# Sheet1.net
KiCad netlist of a schematic drawn in Altium Designer
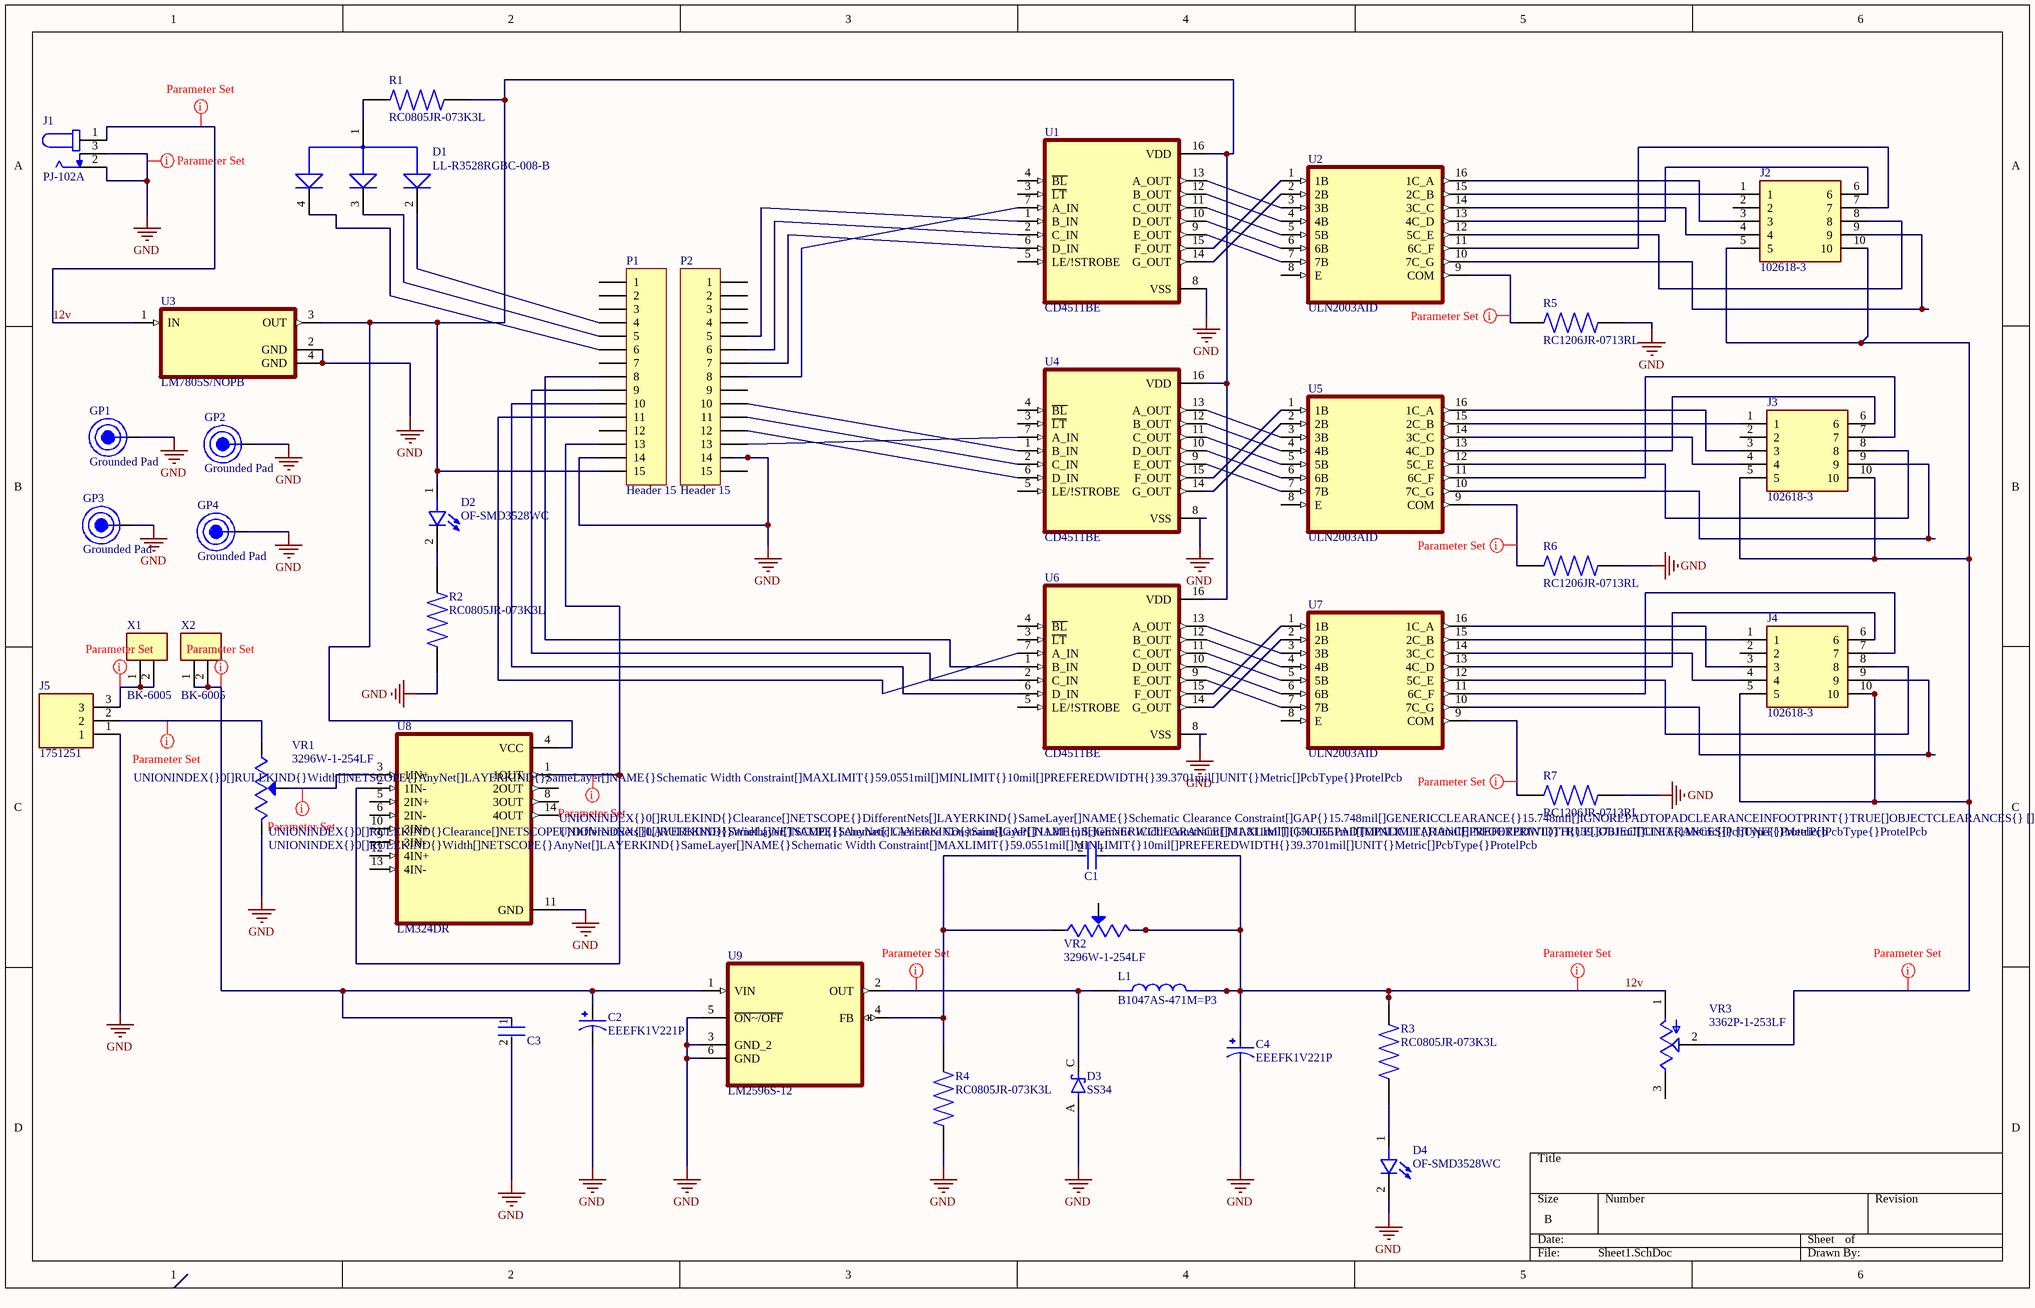
[diagram p0: Sheet1.SchDoc]

(export (version "E")
  (design (tool "Eeschema 10.0.6"))
  (components
    (comp (ref "C1")
      (value "C0805C104K5RAC")
      (footprint "KEMET_C0805C-DN_IPC_C")
      (libsource (lib "Cap_KEMET_C0805C104K5RAC_eec") (part "C0805C104K5RAC"))
    )
    (comp (ref "C2")
      (value "EEEFK1V221P")
      (footprint "CAP_EEEFK1V221P")
      (description "220ÂµF 35V Aluminum Electrolytic Capacitors Radial, Can - SMD 2000 Hrs @ 105Â°C")
      (fields (field (name "MF") "Panasonic"))
      (libsource (lib "EEEFK1V221P") (part "EEEFK1V221P"))
    )
    (comp (ref "C3")
      (value "C0805C104K5RAC")
      (footprint "KEMET_C0805C-DN_IPC_C")
      (libsource (lib "Cap_KEMET_C0805C104K5RAC_eec") (part "C0805C104K5RAC"))
    )
    (comp (ref "C4")
      (value "EEEFK1V221P")
      (footprint "CAP_EEEFK1V221P")
      (description "220ÂµF 35V Aluminum Electrolytic Capacitors Radial, Can - SMD 2000 Hrs @ 105Â°C")
      (fields (field (name "MF") "Panasonic"))
      (libsource (lib "EEEFK1V221P") (part "EEEFK1V221P"))
    )
    (comp (ref "D1")
      (value "LL-R3528RGBC-008-B")
      (footprint "LED_LL-R3528RGBC-008-B")
      (description "LED; SMD; 3528, PLCC2; RGB; 3.5x2.8mm; 120Â°; Red lumin: 1")
      (fields (field (name "MF") "Lucky Light"))
      (libsource (lib "LL-R3528RGBC-008-B") (part "LL-R3528RGBC-008-B"))
    )
    (comp (ref "D2")
      (value "OF-SMD3528WC")
      (footprint "LED_OF-SMD3528WC")
      (description "LED; SMD; 3528, PLCC2; white cold; 1700-2500mcd; 120Â°; 2")
      (fields (field (name "MF") "Optoflash"))
      (libsource (lib "OF-SMD3528WC") (part "OF-SMD3528WC"))
    )
    (comp (ref "D3")
      (value "SS34")
      (footprint "DIOM7959X265N")
      (description "Diode Schottky 40V 3A Surface Mount SMC _DO-214AB_")
      (fields (field (name "MF") "ON Semiconductor"))
      (libsource (lib "SS34") (part "SS34"))
    )
    (comp (ref "D4")
      (value "OF-SMD3528WC")
      (footprint "LED_OF-SMD3528WC")
      (description "LED; SMD; 3528, PLCC2; white cold; 1700-2500mcd; 120Â°; 2")
      (fields (field (name "MF") "Optoflash"))
      (libsource (lib "OF-SMD3528WC") (part "OF-SMD3528WC"))
    )
    (comp (ref "GP1")
      (value "Grounded Pad")
      (footprint "2.75mm Grounded Pad")
      (description "2.75mm Diameter Grounded Pad")
      (libsource (lib "Misc_Tools") (part "2.75mm Grounded Pad"))
    )
    (comp (ref "GP2")
      (value "Grounded Pad")
      (footprint "2.75mm Grounded Pad")
      (description "2.75mm Diameter Grounded Pad")
      (libsource (lib "Misc_Tools") (part "2.75mm Grounded Pad"))
    )
    (comp (ref "GP3")
      (value "Grounded Pad")
      (footprint "2.75mm Grounded Pad")
      (description "2.75mm Diameter Grounded Pad")
      (libsource (lib "Misc_Tools") (part "2.75mm Grounded Pad"))
    )
    (comp (ref "GP4")
      (value "Grounded Pad")
      (footprint "2.75mm Grounded Pad")
      (description "2.75mm Diameter Grounded Pad")
      (libsource (lib "Misc_Tools") (part "2.75mm Grounded Pad"))
    )
    (comp (ref "J1")
      (value "PJ-102A")
      (footprint "CUI_PJ-102A")
      (description "2.0 x 6.5 mm, 2.5 A, Horizontal, Through Hole, Tapered Pins, Dc Power Jack Connector")
      (fields (field (name "MF") "CUI Devices"))
      (libsource (lib "PJ-102A") (part "PJ-102A"))
    )
    (comp (ref "J2")
      (value "102618-3")
      (footprint "TE_102618-3")
      (description "10 MODII HDR DRST SHRD .100CL")
      (libsource (lib "102618-3") (part "102618-3"))
    )
    (comp (ref "J3")
      (value "102618-3")
      (footprint "TE_102618-3")
      (description "10 MODII HDR DRST SHRD .100CL")
      (libsource (lib "102618-3") (part "102618-3"))
    )
    (comp (ref "J4")
      (value "102618-3")
      (footprint "TE_102618-3")
      (description "10 MODII HDR DRST SHRD .100CL")
      (libsource (lib "102618-3") (part "102618-3"))
    )
    (comp (ref "J5")
      (value "1751251")
      (footprint "PHOENIX_1751251")
      (description "3 Position Wire to Board Terminal Block Horizontal with Board 0.138 _3.50mm_ Through Hole")
      (fields (field (name "MF") "Phoenix Contact"))
      (libsource (lib "1751251") (part "1751251"))
    )
    (comp (ref "L1")
      (value "B1047AS-471M=P3")
      (footprint "IND_B1047AS-471M=P3")
      (description "Inductor Power Shielded Wirewound 220uH 20% 100KHz Ferrite 470mA 1.1Ohm DCR 2929 T/R")
      (libsource (lib "B1047AS-471M_P3") (part "B1047AS-471M=P3"))
    )
    (comp (ref "P1")
      (value "Header 15")
      (footprint "HDR1X15")
      (description "Header, 15-Pin")
      (fields (field (name "PUBLISHER") "Altium Limited"))
      (libsource (lib "Miscellaneous Connectors") (part "Header 15"))
    )
    (comp (ref "P2")
      (value "Header 15")
      (footprint "HDR1X15")
      (description "Header, 15-Pin")
      (fields (field (name "PUBLISHER") "Altium Limited"))
      (libsource (lib "") (part "Header 15_1"))
    )
    (comp (ref "R1")
      (value "RC0805JR-073K3L")
      (footprint "RESC2012X60N")
      (description "RC Series 0805 0.125 W 3.3 kOhms 5% Â±100 ppm/Â°C SMT Thick Film Chip Resistor")
      (libsource (lib "RC0805JR-073K3L") (part "RC0805JR-073K3L"))
    )
    (comp (ref "R2")
      (value "RC0805JR-073K3L")
      (footprint "RESC2012X60N")
      (description "RC Series 0805 0.125 W 3.3 kOhms 5% Â±100 ppm/Â°C SMT Thick Film Chip Resistor")
      (libsource (lib "RC0805JR-073K3L") (part "RC0805JR-073K3L"))
    )
    (comp (ref "R3")
      (value "RC0805JR-073K3L")
      (footprint "RESC2012X60N")
      (description "RC Series 0805 0.125 W 3.3 kOhms 5% Â±100 ppm/Â°C SMT Thick Film Chip Resistor")
      (libsource (lib "RC0805JR-073K3L") (part "RC0805JR-073K3L"))
    )
    (comp (ref "R4")
      (value "RC0805JR-073K3L")
      (footprint "RESC2012X60N")
      (description "RC Series 0805 0.125 W 3.3 kOhms 5% Â±100 ppm/Â°C SMT Thick Film Chip Resistor")
      (libsource (lib "RC0805JR-073K3L") (part "RC0805JR-073K3L"))
    )
    (comp (ref "R5")
      (value "RC1206JR-0713RL")
      (footprint "RESC3116X65N")
      (description "13 Ohms Â±5% 0.25W, 1/4W Chip Resistor 1206 _3216 Metric_ Moisture Resistant Thick Film")
      (fields (field (name "MF") "Yageo"))
      (libsource (lib "RC1206JR-0713RL") (part "RC1206JR-0713RL"))
    )
    (comp (ref "R6")
      (value "RC1206JR-0713RL")
      (footprint "RESC3116X65N")
      (description "13 Ohms Â±5% 0.25W, 1/4W Chip Resistor 1206 _3216 Metric_ Moisture Resistant Thick Film")
      (fields (field (name "MF") "Yageo"))
      (libsource (lib "RC1206JR-0713RL") (part "RC1206JR-0713RL"))
    )
    (comp (ref "R7")
      (value "RC1206JR-0713RL")
      (footprint "RESC3116X65N")
      (description "13 Ohms Â±5% 0.25W, 1/4W Chip Resistor 1206 _3216 Metric_ Moisture Resistant Thick Film")
      (fields (field (name "MF") "Yageo"))
      (libsource (lib "RC1206JR-0713RL") (part "RC1206JR-0713RL"))
    )
    (comp (ref "U1")
      (value "CD4511BE")
      (footprint "DIP794W45P254L1969H508Q16")
      (description "CMOS BCD-to-7-Segment LED Latch Decoder Drivers 16-PDIP -55 to 125")
      (fields (field (name "MF") "Texas Instruments"))
      (libsource (lib "CD4511BE") (part "CD4511BE"))
    )
    (comp (ref "U2")
      (value "ULN2003AID")
      (footprint "SOIC127P600X175-16N")
      (description "50-V, 7-ch darlington transistor array, -40 to 105C 16-SOIC -40 to 105")
      (fields (field (name "DIGI-KEY_PART_NUMBER") "296-15407-2-ND") (field (name "MF") "Texas Instruments"))
      (libsource (lib "ULN2003AID") (part "ULN2003AID"))
    )
    (comp (ref "U3")
      (value "LM7805S/NOPB")
      (footprint "TO254P1524X483-4N")
      (description "1.5-A, 30-V, linear voltage regulator 3-DDPAK/TO-263 0 to 125")
      (fields (field (name "MF") "Texas Instruments"))
      (libsource (lib "LM7805S_NOPB") (part "LM7805S/NOPB"))
    )
    (comp (ref "U4")
      (value "CD4511BE")
      (footprint "DIP794W45P254L1969H508Q16")
      (description "CMOS BCD-to-7-Segment LED Latch Decoder Drivers 16-PDIP -55 to 125")
      (fields (field (name "MF") "Texas Instruments"))
      (libsource (lib "CD4511BE") (part "CD4511BE"))
    )
    (comp (ref "U5")
      (value "ULN2003AID")
      (footprint "SOIC127P600X175-16N")
      (description "50-V, 7-ch darlington transistor array, -40 to 105C 16-SOIC -40 to 105")
      (fields (field (name "DIGI-KEY_PART_NUMBER") "296-15407-2-ND") (field (name "MF") "Texas Instruments"))
      (libsource (lib "ULN2003AID") (part "ULN2003AID"))
    )
    (comp (ref "U6")
      (value "CD4511BE")
      (footprint "DIP794W45P254L1969H508Q16")
      (description "CMOS BCD-to-7-Segment LED Latch Decoder Drivers 16-PDIP -55 to 125")
      (fields (field (name "MF") "Texas Instruments"))
      (libsource (lib "CD4511BE") (part "CD4511BE"))
    )
    (comp (ref "U7")
      (value "ULN2003AID")
      (footprint "SOIC127P600X175-16N")
      (description "50-V, 7-ch darlington transistor array, -40 to 105C 16-SOIC -40 to 105")
      (fields (field (name "DIGI-KEY_PART_NUMBER") "296-15407-2-ND") (field (name "MF") "Texas Instruments"))
      (libsource (lib "ULN2003AID") (part "ULN2003AID"))
    )
    (comp (ref "U8")
      (value "LM324DR")
      (footprint "SOIC127P600X175-14N")
      (description "4-Channel industry standard operational amplifier 14-SOIC 0 to 70")
      (fields (field (name "MF") "Texas Instruments"))
      (libsource (lib "LM324DR") (part "LM324DR"))
    )
    (comp (ref "U9")
      (value "LM2596S-12")
      (footprint "TO170P1435X465-6N")
      (fields (field (name "MF") "Texas Instruments"))
      (libsource (lib "LM2596S-12") (part "LM2596S-12"))
    )
    (comp (ref "VR1")
      (value "3296W-1-254LF")
      (footprint "TRIM_3296W-1-254LF")
      (description "250 kOhms 0.5W, 1/2W PC Pins Through Hole Trimmer Potentiometer Cermet 25 Turn Top Adjustment")
      (fields (field (name "MF") "Bourns"))
      (libsource (lib "3296W-1-254LF") (part "3296W-1-254LF"))
    )
    (comp (ref "VR2")
      (value "3296W-1-254LF")
      (footprint "TRIM_3296W-1-254LF")
      (description "250 kOhms 0.5W, 1/2W PC Pins Through Hole Trimmer Potentiometer Cermet 25 Turn Top Adjustment")
      (fields (field (name "MF") "Bourns"))
      (libsource (lib "3296W-1-254LF") (part "3296W-1-254LF"))
    )
    (comp (ref "VR3")
      (value "3362P-1-253LF")
      (footprint "TRIM_3362P-1-253LF")
      (description "25 kOhms 0.5W, 1/2W PC Pins Through Hole Trimmer Potentiometer Cermet 1 Turn Top Adjustment")
      (fields (field (name "MF") "Bourns"))
      (libsource (lib "3362P-1-253LF") (part "3362P-1-253LF"))
    )
    (comp (ref "X1")
      (value "BK-6005")
      (footprint "FUSE_BK-6005")
      (description "Fuse Clip 1 Circuit Cartridge Through Hole")
      (fields (field (name "MF") "MPD"))
      (libsource (lib "BK-6005") (part "BK-6005"))
    )
    (comp (ref "X2")
      (value "BK-6005")
      (footprint "FUSE_BK-6005")
      (description "Fuse Clip 1 Circuit Cartridge Through Hole")
      (fields (field (name "MF") "MPD"))
      (libsource (lib "BK-6005") (part "BK-6005"))
    )
  )
  (nets
    (net (code "1") (name "/12v") (class "Default")
      (node (ref "C1") (pin "1") (pinfunction "1_1") (pintype "passive"))
      (node (ref "C4") (pin "1") (pinfunction "1_1") (pintype "passive"))
      (node (ref "J1") (pin "1") (pinfunction "1_1") (pintype "passive"))
      (node (ref "L1") (pin "2") (pinfunction "2_2") (pintype "passive"))
      (node (ref "R3") (pin "2") (pinfunction "2_2") (pintype "passive"))
      (node (ref "U3") (pin "1") (pinfunction "IN_1") (pintype "input"))
      (node (ref "VR2") (pin "3") (pinfunction "CW_3") (pintype "passive"))
      (node (ref "VR3") (pin "1") (pinfunction "CCW_1") (pintype "passive"))
    )
    (net (code "2") (name "GND") (class "Default")
      (node (ref "C2") (pin "2") (pinfunction "2_2") (pintype "passive"))
      (node (ref "C3") (pin "2") (pinfunction "2_2") (pintype "passive"))
      (node (ref "C4") (pin "2") (pinfunction "2_2") (pintype "passive"))
      (node (ref "D3") (pin "A") (pinfunction "A_A") (pintype "passive"))
      (node (ref "D4") (pin "2") (pinfunction "C_2") (pintype "passive"))
      (node (ref "GP1") (pin "1") (pinfunction "1_1") (pintype "passive"))
      (node (ref "GP2") (pin "1") (pinfunction "1_1") (pintype "passive"))
      (node (ref "GP3") (pin "1") (pinfunction "1_1") (pintype "passive"))
      (node (ref "GP4") (pin "1") (pinfunction "1_1") (pintype "passive"))
      (node (ref "J1") (pin "2") (pinfunction "2_2") (pintype "passive"))
      (node (ref "J1") (pin "3") (pinfunction "3_3") (pintype "passive"))
      (node (ref "J5") (pin "1") (pinfunction "1_1") (pintype "passive"))
      (node (ref "P1") (pin "14") (pinfunction "14_14") (pintype "passive"))
      (node (ref "P2") (pin "14") (pinfunction "14_14") (pintype "passive"))
      (node (ref "R2") (pin "1") (pinfunction "1_1") (pintype "passive"))
      (node (ref "R4") (pin "1") (pinfunction "1_1") (pintype "passive"))
      (node (ref "R5") (pin "2") (pinfunction "2_2") (pintype "passive"))
      (node (ref "R6") (pin "2") (pinfunction "2_2") (pintype "passive"))
      (node (ref "R7") (pin "2") (pinfunction "2_2") (pintype "passive"))
      (node (ref "U1") (pin "8") (pinfunction "VSS_8") (pintype "power_in"))
      (node (ref "U3") (pin "2") (pinfunction "GND_2") (pintype "power_in"))
      (node (ref "U3") (pin "4") (pinfunction "GND_4") (pintype "power_in"))
      (node (ref "U4") (pin "8") (pinfunction "VSS_8") (pintype "power_in"))
      (node (ref "U6") (pin "8") (pinfunction "VSS_8") (pintype "power_in"))
      (node (ref "U8") (pin "11") (pinfunction "GND_11") (pintype "power_in"))
      (node (ref "U9") (pin "3") (pinfunction "GND_2_3") (pintype "passive"))
      (node (ref "U9") (pin "5") (pinfunction "~{ON~/OFF}_5") (pintype "passive"))
      (node (ref "U9") (pin "6") (pinfunction "GND_6") (pintype "passive"))
      (node (ref "VR1") (pin "3") (pinfunction "CW_3") (pintype "passive"))
    )
    (net (code "3") (name "Net-(D1-CATHODE_BLUE)") (class "Default")
      (node (ref "D1") (pin "4") (pinfunction "CATHODE_BLUE_4") (pintype "passive"))
      (node (ref "P1") (pin "6") (pinfunction "6_6") (pintype "passive"))
    )
    (net (code "4") (name "Net-(D1-CATHODE_GREEN)") (class "Default")
      (node (ref "D1") (pin "3") (pinfunction "CATHODE_GREEN_3") (pintype "passive"))
      (node (ref "P1") (pin "5") (pinfunction "5_5") (pintype "passive"))
    )
    (net (code "5") (name "Net-(D1-CATHODE_RED)") (class "Default")
      (node (ref "D1") (pin "2") (pinfunction "CATHODE_RED_2") (pintype "passive"))
      (node (ref "P1") (pin "4") (pinfunction "4_4") (pintype "passive"))
    )
    (net (code "6") (name "Net-(D1-COMM_ANODE)") (class "Default")
      (node (ref "D1") (pin "1") (pinfunction "COMM_ANODE_1") (pintype "passive"))
      (node (ref "R1") (pin "2") (pinfunction "2_2") (pintype "passive"))
    )
    (net (code "7") (name "Net-(D2-A)") (class "Default")
      (node (ref "D2") (pin "1") (pinfunction "A_1") (pintype "passive"))
      (node (ref "P1") (pin "15") (pinfunction "15_15") (pintype "passive"))
      (node (ref "R1") (pin "1") (pinfunction "1_1") (pintype "passive"))
      (node (ref "U1") (pin "16") (pinfunction "VDD_16") (pintype "power_in"))
      (node (ref "U3") (pin "3") (pinfunction "OUT_3") (pintype "output"))
      (node (ref "U4") (pin "16") (pinfunction "VDD_16") (pintype "power_in"))
      (node (ref "U6") (pin "16") (pinfunction "VDD_16") (pintype "power_in"))
      (node (ref "U8") (pin "4") (pinfunction "VCC_4") (pintype "power_in"))
    )
    (net (code "8") (name "Net-(D2-C)") (class "Default")
      (node (ref "D2") (pin "2") (pinfunction "C_2") (pintype "passive"))
      (node (ref "R2") (pin "2") (pinfunction "2_2") (pintype "passive"))
    )
    (net (code "9") (name "Net-(D3-K)") (class "Default")
      (node (ref "D3") (pin "C") (pinfunction "K_C") (pintype "passive"))
      (node (ref "L1") (pin "1") (pinfunction "1_1") (pintype "passive"))
      (node (ref "U9") (pin "2") (pinfunction "OUT_2") (pintype "output"))
    )
    (net (code "10") (name "Net-(D4-A)") (class "Default")
      (node (ref "D4") (pin "1") (pinfunction "A_1") (pintype "passive"))
      (node (ref "R3") (pin "1") (pinfunction "1_1") (pintype "passive"))
    )
    (net (code "11") (name "Net-(J5-Pad3)") (class "Default")
      (node (ref "J5") (pin "3") (pinfunction "3_3") (pintype "passive"))
      (node (ref "X1") (pin "1") (pinfunction "1_1") (pintype "passive"))
      (node (ref "X1") (pin "2") (pinfunction "1_2") (pintype "passive"))
    )
    (net (code "12") (name "Net-(U1-A_IN)") (class "Default")
      (node (ref "P2") (pin "8") (pinfunction "8_8") (pintype "passive"))
      (node (ref "U1") (pin "7") (pinfunction "A_IN_7") (pintype "input"))
    )
    (net (code "13") (name "Net-(U1-A_OUT)") (class "Default")
      (node (ref "U1") (pin "13") (pinfunction "A_OUT_13") (pintype "output"))
      (node (ref "U2") (pin "3") (pinfunction "3B_3") (pintype "input"))
    )
    (net (code "14") (name "Net-(U1-B_IN)") (class "Default")
      (node (ref "P2") (pin "5") (pinfunction "5_5") (pintype "passive"))
      (node (ref "U1") (pin "1") (pinfunction "B_IN_1") (pintype "input"))
    )
    (net (code "15") (name "Net-(U1-B_OUT)") (class "Default")
      (node (ref "U1") (pin "12") (pinfunction "B_OUT_12") (pintype "output"))
      (node (ref "U2") (pin "4") (pinfunction "4B_4") (pintype "input"))
    )
    (net (code "16") (name "Net-(U1-C_IN)") (class "Default")
      (node (ref "P2") (pin "6") (pinfunction "6_6") (pintype "passive"))
      (node (ref "U1") (pin "2") (pinfunction "C_IN_2") (pintype "input"))
    )
    (net (code "17") (name "Net-(U1-C_OUT)") (class "Default")
      (node (ref "U1") (pin "11") (pinfunction "C_OUT_11") (pintype "output"))
      (node (ref "U2") (pin "5") (pinfunction "5B_5") (pintype "input"))
    )
    (net (code "18") (name "Net-(U1-D_IN)") (class "Default")
      (node (ref "P2") (pin "7") (pinfunction "7_7") (pintype "passive"))
      (node (ref "U1") (pin "6") (pinfunction "D_IN_6") (pintype "input"))
    )
    (net (code "19") (name "Net-(U1-D_OUT)") (class "Default")
      (node (ref "U1") (pin "10") (pinfunction "D_OUT_10") (pintype "output"))
      (node (ref "U2") (pin "6") (pinfunction "6B_6") (pintype "input"))
    )
    (net (code "20") (name "Net-(U1-E_OUT)") (class "Default")
      (node (ref "U1") (pin "9") (pinfunction "E_OUT_9") (pintype "output"))
      (node (ref "U2") (pin "7") (pinfunction "7B_7") (pintype "input"))
    )
    (net (code "21") (name "Net-(U1-F_OUT)") (class "Default")
      (node (ref "U1") (pin "15") (pinfunction "F_OUT_15") (pintype "output"))
      (node (ref "U2") (pin "1") (pinfunction "1B_1") (pintype "input"))
    )
    (net (code "22") (name "Net-(U1-G_OUT)") (class "Default")
      (node (ref "U1") (pin "14") (pinfunction "G_OUT_14") (pintype "output"))
      (node (ref "U2") (pin "2") (pinfunction "2B_2") (pintype "input"))
    )
    (net (code "23") (name "Net-(U2-1C_A)") (class "Default")
      (node (ref "J2") (pin "3") (pinfunction "3_3") (pintype "passive"))
      (node (ref "U2") (pin "16") (pinfunction "1C_A_16") (pintype "output"))
    )
    (net (code "24") (name "Net-(U2-2C_B)") (class "Default")
      (node (ref "J2") (pin "1") (pinfunction "1_1") (pintype "passive"))
      (node (ref "U2") (pin "15") (pinfunction "2C_B_15") (pintype "output"))
    )
    (net (code "25") (name "Net-(U2-3C_C)") (class "Default")
      (node (ref "J2") (pin "4") (pinfunction "4_4") (pintype "passive"))
      (node (ref "U2") (pin "14") (pinfunction "3C_C_14") (pintype "output"))
    )
    (net (code "26") (name "Net-(U2-4C_D)") (class "Default")
      (node (ref "J2") (pin "6") (pinfunction "6_6") (pintype "passive"))
      (node (ref "U2") (pin "13") (pinfunction "4C_D_13") (pintype "output"))
    )
    (net (code "27") (name "Net-(U2-5C_E)") (class "Default")
      (node (ref "J2") (pin "8") (pinfunction "8_8") (pintype "passive"))
      (node (ref "U2") (pin "12") (pinfunction "5C_E_12") (pintype "output"))
    )
    (net (code "28") (name "Net-(U2-6C_F)") (class "Default")
      (node (ref "J2") (pin "7") (pinfunction "7_7") (pintype "passive"))
      (node (ref "U2") (pin "11") (pinfunction "6C_F_11") (pintype "output"))
    )
    (net (code "29") (name "Net-(U2-7C_G)") (class "Default")
      (node (ref "J2") (pin "9") (pinfunction "9_9") (pintype "passive"))
      (node (ref "U2") (pin "10") (pinfunction "7C_G_10") (pintype "output"))
    )
    (net (code "30") (name "Net-(U2-COM)") (class "Default")
      (node (ref "R5") (pin "1") (pinfunction "1_1") (pintype "passive"))
      (node (ref "U2") (pin "9") (pinfunction "COM_9") (pintype "output"))
    )
    (net (code "31") (name "Net-(U4-A_IN)") (class "Default")
      (node (ref "P2") (pin "13") (pinfunction "13_13") (pintype "passive"))
      (node (ref "U4") (pin "7") (pinfunction "A_IN_7") (pintype "input"))
    )
    (net (code "32") (name "Net-(U4-A_OUT)") (class "Default")
      (node (ref "U4") (pin "13") (pinfunction "A_OUT_13") (pintype "output"))
      (node (ref "U5") (pin "3") (pinfunction "3B_3") (pintype "input"))
    )
    (net (code "33") (name "Net-(U4-B_IN)") (class "Default")
      (node (ref "P2") (pin "10") (pinfunction "10_10") (pintype "passive"))
      (node (ref "U4") (pin "1") (pinfunction "B_IN_1") (pintype "input"))
    )
    (net (code "34") (name "Net-(U4-B_OUT)") (class "Default")
      (node (ref "U4") (pin "12") (pinfunction "B_OUT_12") (pintype "output"))
      (node (ref "U5") (pin "4") (pinfunction "4B_4") (pintype "input"))
    )
    (net (code "35") (name "Net-(U4-C_IN)") (class "Default")
      (node (ref "P2") (pin "11") (pinfunction "11_11") (pintype "passive"))
      (node (ref "U4") (pin "2") (pinfunction "C_IN_2") (pintype "input"))
    )
    (net (code "36") (name "Net-(U4-C_OUT)") (class "Default")
      (node (ref "U4") (pin "11") (pinfunction "C_OUT_11") (pintype "output"))
      (node (ref "U5") (pin "5") (pinfunction "5B_5") (pintype "input"))
    )
    (net (code "37") (name "Net-(U4-D_IN)") (class "Default")
      (node (ref "P2") (pin "12") (pinfunction "12_12") (pintype "passive"))
      (node (ref "U4") (pin "6") (pinfunction "D_IN_6") (pintype "input"))
    )
    (net (code "38") (name "Net-(U4-D_OUT)") (class "Default")
      (node (ref "U4") (pin "10") (pinfunction "D_OUT_10") (pintype "output"))
      (node (ref "U5") (pin "6") (pinfunction "6B_6") (pintype "input"))
    )
    (net (code "39") (name "Net-(U4-E_OUT)") (class "Default")
      (node (ref "U4") (pin "9") (pinfunction "E_OUT_9") (pintype "output"))
      (node (ref "U5") (pin "7") (pinfunction "7B_7") (pintype "input"))
    )
    (net (code "40") (name "Net-(U4-F_OUT)") (class "Default")
      (node (ref "U4") (pin "15") (pinfunction "F_OUT_15") (pintype "output"))
      (node (ref "U5") (pin "1") (pinfunction "1B_1") (pintype "input"))
    )
    (net (code "41") (name "Net-(U4-G_OUT)") (class "Default")
      (node (ref "U4") (pin "14") (pinfunction "G_OUT_14") (pintype "output"))
      (node (ref "U5") (pin "2") (pinfunction "2B_2") (pintype "input"))
    )
    (net (code "42") (name "Net-(U5-1C_A)") (class "Default")
      (node (ref "J3") (pin "3") (pinfunction "3_3") (pintype "passive"))
      (node (ref "U5") (pin "16") (pinfunction "1C_A_16") (pintype "output"))
    )
    (net (code "43") (name "Net-(U5-2C_B)") (class "Default")
      (node (ref "J3") (pin "1") (pinfunction "1_1") (pintype "passive"))
      (node (ref "U5") (pin "15") (pinfunction "2C_B_15") (pintype "output"))
    )
    (net (code "44") (name "Net-(U5-3C_C)") (class "Default")
      (node (ref "J3") (pin "4") (pinfunction "4_4") (pintype "passive"))
      (node (ref "U5") (pin "14") (pinfunction "3C_C_14") (pintype "output"))
    )
    (net (code "45") (name "Net-(U5-4C_D)") (class "Default")
      (node (ref "J3") (pin "6") (pinfunction "6_6") (pintype "passive"))
      (node (ref "U5") (pin "13") (pinfunction "4C_D_13") (pintype "output"))
    )
    (net (code "46") (name "Net-(U5-5C_E)") (class "Default")
      (node (ref "J3") (pin "8") (pinfunction "8_8") (pintype "passive"))
      (node (ref "U5") (pin "12") (pinfunction "5C_E_12") (pintype "output"))
    )
    (net (code "47") (name "Net-(U5-6C_F)") (class "Default")
      (node (ref "J3") (pin "7") (pinfunction "7_7") (pintype "passive"))
      (node (ref "U5") (pin "11") (pinfunction "6C_F_11") (pintype "output"))
    )
    (net (code "48") (name "Net-(U5-7C_G)") (class "Default")
      (node (ref "J3") (pin "9") (pinfunction "9_9") (pintype "passive"))
      (node (ref "U5") (pin "10") (pinfunction "7C_G_10") (pintype "output"))
    )
    (net (code "49") (name "Net-(U5-COM)") (class "Default")
      (node (ref "R6") (pin "1") (pinfunction "1_1") (pintype "passive"))
      (node (ref "U5") (pin "9") (pinfunction "COM_9") (pintype "output"))
    )
    (net (code "50") (name "Net-(U6-A_IN)") (class "Default")
      (node (ref "P1") (pin "11") (pinfunction "11_11") (pintype "passive"))
      (node (ref "U6") (pin "7") (pinfunction "A_IN_7") (pintype "input"))
    )
    (net (code "51") (name "Net-(U6-A_OUT)") (class "Default")
      (node (ref "U6") (pin "13") (pinfunction "A_OUT_13") (pintype "output"))
      (node (ref "U7") (pin "3") (pinfunction "3B_3") (pintype "input"))
    )
    (net (code "52") (name "Net-(U6-B_IN)") (class "Default")
      (node (ref "P1") (pin "8") (pinfunction "8_8") (pintype "passive"))
      (node (ref "U6") (pin "1") (pinfunction "B_IN_1") (pintype "input"))
    )
    (net (code "53") (name "Net-(U6-B_OUT)") (class "Default")
      (node (ref "U6") (pin "12") (pinfunction "B_OUT_12") (pintype "output"))
      (node (ref "U7") (pin "4") (pinfunction "4B_4") (pintype "input"))
    )
    (net (code "54") (name "Net-(U6-C_IN)") (class "Default")
      (node (ref "P1") (pin "9") (pinfunction "9_9") (pintype "passive"))
      (node (ref "U6") (pin "2") (pinfunction "C_IN_2") (pintype "input"))
    )
    (net (code "55") (name "Net-(U6-C_OUT)") (class "Default")
      (node (ref "U6") (pin "11") (pinfunction "C_OUT_11") (pintype "output"))
      (node (ref "U7") (pin "5") (pinfunction "5B_5") (pintype "input"))
    )
    (net (code "56") (name "Net-(U6-D_IN)") (class "Default")
      (node (ref "P1") (pin "10") (pinfunction "10_10") (pintype "passive"))
      (node (ref "U6") (pin "6") (pinfunction "D_IN_6") (pintype "input"))
    )
    (net (code "57") (name "Net-(U6-D_OUT)") (class "Default")
      (node (ref "U6") (pin "10") (pinfunction "D_OUT_10") (pintype "output"))
      (node (ref "U7") (pin "6") (pinfunction "6B_6") (pintype "input"))
    )
    (net (code "58") (name "Net-(U6-E_OUT)") (class "Default")
      (node (ref "U6") (pin "9") (pinfunction "E_OUT_9") (pintype "output"))
      (node (ref "U7") (pin "7") (pinfunction "7B_7") (pintype "input"))
    )
    (net (code "59") (name "Net-(U6-F_OUT)") (class "Default")
      (node (ref "U6") (pin "15") (pinfunction "F_OUT_15") (pintype "output"))
      (node (ref "U7") (pin "1") (pinfunction "1B_1") (pintype "input"))
    )
    (net (code "60") (name "Net-(U6-G_OUT)") (class "Default")
      (node (ref "U6") (pin "14") (pinfunction "G_OUT_14") (pintype "output"))
      (node (ref "U7") (pin "2") (pinfunction "2B_2") (pintype "input"))
    )
    (net (code "61") (name "Net-(U7-1C_A)") (class "Default")
      (node (ref "J4") (pin "3") (pinfunction "3_3") (pintype "passive"))
      (node (ref "U7") (pin "16") (pinfunction "1C_A_16") (pintype "output"))
    )
    (net (code "62") (name "Net-(U7-2C_B)") (class "Default")
      (node (ref "J4") (pin "1") (pinfunction "1_1") (pintype "passive"))
      (node (ref "U7") (pin "15") (pinfunction "2C_B_15") (pintype "output"))
    )
    (net (code "63") (name "Net-(U7-3C_C)") (class "Default")
      (node (ref "J4") (pin "4") (pinfunction "4_4") (pintype "passive"))
      (node (ref "U7") (pin "14") (pinfunction "3C_C_14") (pintype "output"))
    )
    (net (code "64") (name "Net-(U7-4C_D)") (class "Default")
      (node (ref "J4") (pin "6") (pinfunction "6_6") (pintype "passive"))
      (node (ref "U7") (pin "13") (pinfunction "4C_D_13") (pintype "output"))
    )
    (net (code "65") (name "Net-(U7-5C_E)") (class "Default")
      (node (ref "J4") (pin "8") (pinfunction "8_8") (pintype "passive"))
      (node (ref "U7") (pin "12") (pinfunction "5C_E_12") (pintype "output"))
    )
    (net (code "66") (name "Net-(U7-6C_F)") (class "Default")
      (node (ref "J4") (pin "7") (pinfunction "7_7") (pintype "passive"))
      (node (ref "U7") (pin "11") (pinfunction "6C_F_11") (pintype "output"))
    )
    (net (code "67") (name "Net-(U7-7C_G)") (class "Default")
      (node (ref "J4") (pin "9") (pinfunction "9_9") (pintype "passive"))
      (node (ref "U7") (pin "10") (pinfunction "7C_G_10") (pintype "output"))
    )
    (net (code "68") (name "Net-(U7-COM)") (class "Default")
      (node (ref "R7") (pin "1") (pinfunction "1_1") (pintype "passive"))
      (node (ref "U7") (pin "9") (pinfunction "COM_9") (pintype "output"))
    )
    (net (code "69") (name "Net-(U8-1IN+)") (class "Default")
      (node (ref "U8") (pin "3") (pinfunction "1IN+_3") (pintype "input"))
      (node (ref "VR1") (pin "2") (pinfunction "WIPER_2") (pintype "passive"))
    )
    (net (code "70") (name "Net-(U8-1IN-)") (class "Default")
      (node (ref "P1") (pin "13") (pinfunction "13_13") (pintype "passive"))
      (node (ref "U8") (pin "1") (pinfunction "1OUT_1") (pintype "output"))
      (node (ref "U8") (pin "2") (pinfunction "1IN-_2") (pintype "input"))
    )
    (net (code "71") (name "Net-(U9-FB)") (class "Default")
      (node (ref "C1") (pin "2") (pinfunction "2_2") (pintype "passive"))
      (node (ref "R4") (pin "2") (pinfunction "2_2") (pintype "passive"))
      (node (ref "U9") (pin "4") (pinfunction "FB_4") (pintype "bidirectional"))
      (node (ref "VR2") (pin "1") (pinfunction "CCW_1") (pintype "passive"))
    )
    (net (code "72") (name "Net-(U9-VIN)") (class "Default")
      (node (ref "C2") (pin "1") (pinfunction "1_1") (pintype "passive"))
      (node (ref "C3") (pin "1") (pinfunction "1_1") (pintype "passive"))
      (node (ref "U9") (pin "1") (pinfunction "VIN_1") (pintype "input"))
      (node (ref "X2") (pin "1") (pinfunction "1_1") (pintype "passive"))
      (node (ref "X2") (pin "2") (pinfunction "1_2") (pintype "passive"))
    )
    (net (code "73") (name "Net-(VR1-CCW)") (class "Default")
      (node (ref "J5") (pin "2") (pinfunction "2_2") (pintype "passive"))
      (node (ref "VR1") (pin "1") (pinfunction "CCW_1") (pintype "passive"))
    )
    (net (code "74") (name "Net-(VR3-WIPER)") (class "Default")
      (node (ref "J2") (pin "10") (pinfunction "10_10") (pintype "passive"))
      (node (ref "J2") (pin "5") (pinfunction "5_5") (pintype "passive"))
      (node (ref "J3") (pin "10") (pinfunction "10_10") (pintype "passive"))
      (node (ref "J3") (pin "5") (pinfunction "5_5") (pintype "passive"))
      (node (ref "J4") (pin "10") (pinfunction "10_10") (pintype "passive"))
      (node (ref "J4") (pin "5") (pinfunction "5_5") (pintype "passive"))
      (node (ref "VR3") (pin "2") (pinfunction "WIPER_2") (pintype "passive"))
    )
    (net (code "75") (name "unconnected-(J2-Pad2)") (class "Default")
      (node (ref "J2") (pin "2") (pinfunction "2_2") (pintype "passive"))
    )
    (net (code "76") (name "unconnected-(J3-Pad2)") (class "Default")
      (node (ref "J3") (pin "2") (pinfunction "2_2") (pintype "passive"))
    )
    (net (code "77") (name "unconnected-(J4-Pad2)") (class "Default")
      (node (ref "J4") (pin "2") (pinfunction "2_2") (pintype "passive"))
    )
    (net (code "78") (name "unconnected-(P1-Pad1)") (class "Default")
      (node (ref "P1") (pin "1") (pinfunction "1_1") (pintype "passive"))
    )
    (net (code "79") (name "unconnected-(P1-Pad2)") (class "Default")
      (node (ref "P1") (pin "2") (pinfunction "2_2") (pintype "passive"))
    )
    (net (code "80") (name "unconnected-(P1-Pad3)") (class "Default")
      (node (ref "P1") (pin "3") (pinfunction "3_3") (pintype "passive"))
    )
    (net (code "81") (name "unconnected-(P1-Pad7)") (class "Default")
      (node (ref "P1") (pin "7") (pinfunction "7_7") (pintype "passive"))
    )
    (net (code "82") (name "unconnected-(P1-Pad12)") (class "Default")
      (node (ref "P1") (pin "12") (pinfunction "12_12") (pintype "passive"))
    )
    (net (code "83") (name "unconnected-(P2-Pad1)") (class "Default")
      (node (ref "P2") (pin "1") (pinfunction "1_1") (pintype "passive"))
    )
    (net (code "84") (name "unconnected-(P2-Pad2)") (class "Default")
      (node (ref "P2") (pin "2") (pinfunction "2_2") (pintype "passive"))
    )
    (net (code "85") (name "unconnected-(P2-Pad3)") (class "Default")
      (node (ref "P2") (pin "3") (pinfunction "3_3") (pintype "passive"))
    )
    (net (code "86") (name "unconnected-(P2-Pad4)") (class "Default")
      (node (ref "P2") (pin "4") (pinfunction "4_4") (pintype "passive"))
    )
    (net (code "87") (name "unconnected-(P2-Pad9)") (class "Default")
      (node (ref "P2") (pin "9") (pinfunction "9_9") (pintype "passive"))
    )
    (net (code "88") (name "unconnected-(P2-Pad15)") (class "Default")
      (node (ref "P2") (pin "15") (pinfunction "15_15") (pintype "passive"))
    )
    (net (code "89") (name "unconnected-(U1-LE{slash}!STROBE-Pad5)") (class "Default")
      (node (ref "U1") (pin "5") (pinfunction "LE/!STROBE_5") (pintype "input"))
    )
    (net (code "90") (name "unconnected-(U1-~{BL}-Pad4)") (class "Default")
      (node (ref "U1") (pin "4") (pinfunction "~{BL}_4") (pintype "input"))
    )
    (net (code "91") (name "unconnected-(U1-~{LT}-Pad3)") (class "Default")
      (node (ref "U1") (pin "3") (pinfunction "~{LT}_3") (pintype "input"))
    )
    (net (code "92") (name "unconnected-(U2-E-Pad8)") (class "Default")
      (node (ref "U2") (pin "8") (pinfunction "E_8") (pintype "input"))
    )
    (net (code "93") (name "unconnected-(U4-LE{slash}!STROBE-Pad5)") (class "Default")
      (node (ref "U4") (pin "5") (pinfunction "LE/!STROBE_5") (pintype "input"))
    )
    (net (code "94") (name "unconnected-(U4-~{BL}-Pad4)") (class "Default")
      (node (ref "U4") (pin "4") (pinfunction "~{BL}_4") (pintype "input"))
    )
    (net (code "95") (name "unconnected-(U4-~{LT}-Pad3)") (class "Default")
      (node (ref "U4") (pin "3") (pinfunction "~{LT}_3") (pintype "input"))
    )
    (net (code "96") (name "unconnected-(U5-E-Pad8)") (class "Default")
      (node (ref "U5") (pin "8") (pinfunction "E_8") (pintype "input"))
    )
    (net (code "97") (name "unconnected-(U6-LE{slash}!STROBE-Pad5)") (class "Default")
      (node (ref "U6") (pin "5") (pinfunction "LE/!STROBE_5") (pintype "input"))
    )
    (net (code "98") (name "unconnected-(U6-~{BL}-Pad4)") (class "Default")
      (node (ref "U6") (pin "4") (pinfunction "~{BL}_4") (pintype "input"))
    )
    (net (code "99") (name "unconnected-(U6-~{LT}-Pad3)") (class "Default")
      (node (ref "U6") (pin "3") (pinfunction "~{LT}_3") (pintype "input"))
    )
    (net (code "100") (name "unconnected-(U7-E-Pad8)") (class "Default")
      (node (ref "U7") (pin "8") (pinfunction "E_8") (pintype "input"))
    )
    (net (code "101") (name "unconnected-(U8-2IN+-Pad5)") (class "Default")
      (node (ref "U8") (pin "5") (pinfunction "2IN+_5") (pintype "input"))
    )
    (net (code "102") (name "unconnected-(U8-2IN--Pad6)") (class "Default")
      (node (ref "U8") (pin "6") (pinfunction "2IN-_6") (pintype "input"))
    )
    (net (code "103") (name "unconnected-(U8-2OUT-Pad7)") (class "Default")
      (node (ref "U8") (pin "7") (pinfunction "2OUT_7") (pintype "output"))
    )
    (net (code "104") (name "unconnected-(U8-3IN+-Pad10)") (class "Default")
      (node (ref "U8") (pin "10") (pinfunction "3IN+_10") (pintype "input"))
    )
    (net (code "105") (name "unconnected-(U8-3IN--Pad9)") (class "Default")
      (node (ref "U8") (pin "9") (pinfunction "3IN-_9") (pintype "input"))
    )
    (net (code "106") (name "unconnected-(U8-3OUT-Pad8)") (class "Default")
      (node (ref "U8") (pin "8") (pinfunction "3OUT_8") (pintype "output"))
    )
    (net (code "107") (name "unconnected-(U8-4IN+-Pad12)") (class "Default")
      (node (ref "U8") (pin "12") (pinfunction "4IN+_12") (pintype "input"))
    )
    (net (code "108") (name "unconnected-(U8-4IN--Pad13)") (class "Default")
      (node (ref "U8") (pin "13") (pinfunction "4IN-_13") (pintype "input"))
    )
    (net (code "109") (name "unconnected-(U8-4OUT-Pad14)") (class "Default")
      (node (ref "U8") (pin "14") (pinfunction "4OUT_14") (pintype "output"))
    )
    (net (code "110") (name "unconnected-(VR2-WIPER-Pad2)") (class "Default")
      (node (ref "VR2") (pin "2") (pinfunction "WIPER_2") (pintype "passive"))
    )
    (net (code "111") (name "unconnected-(VR3-CW-Pad3)") (class "Default")
      (node (ref "VR3") (pin "3") (pinfunction "CW_3") (pintype "passive"))
    )
  )
)
